# Sheet2.net
KiCad netlist of a schematic drawn in Altium Designer
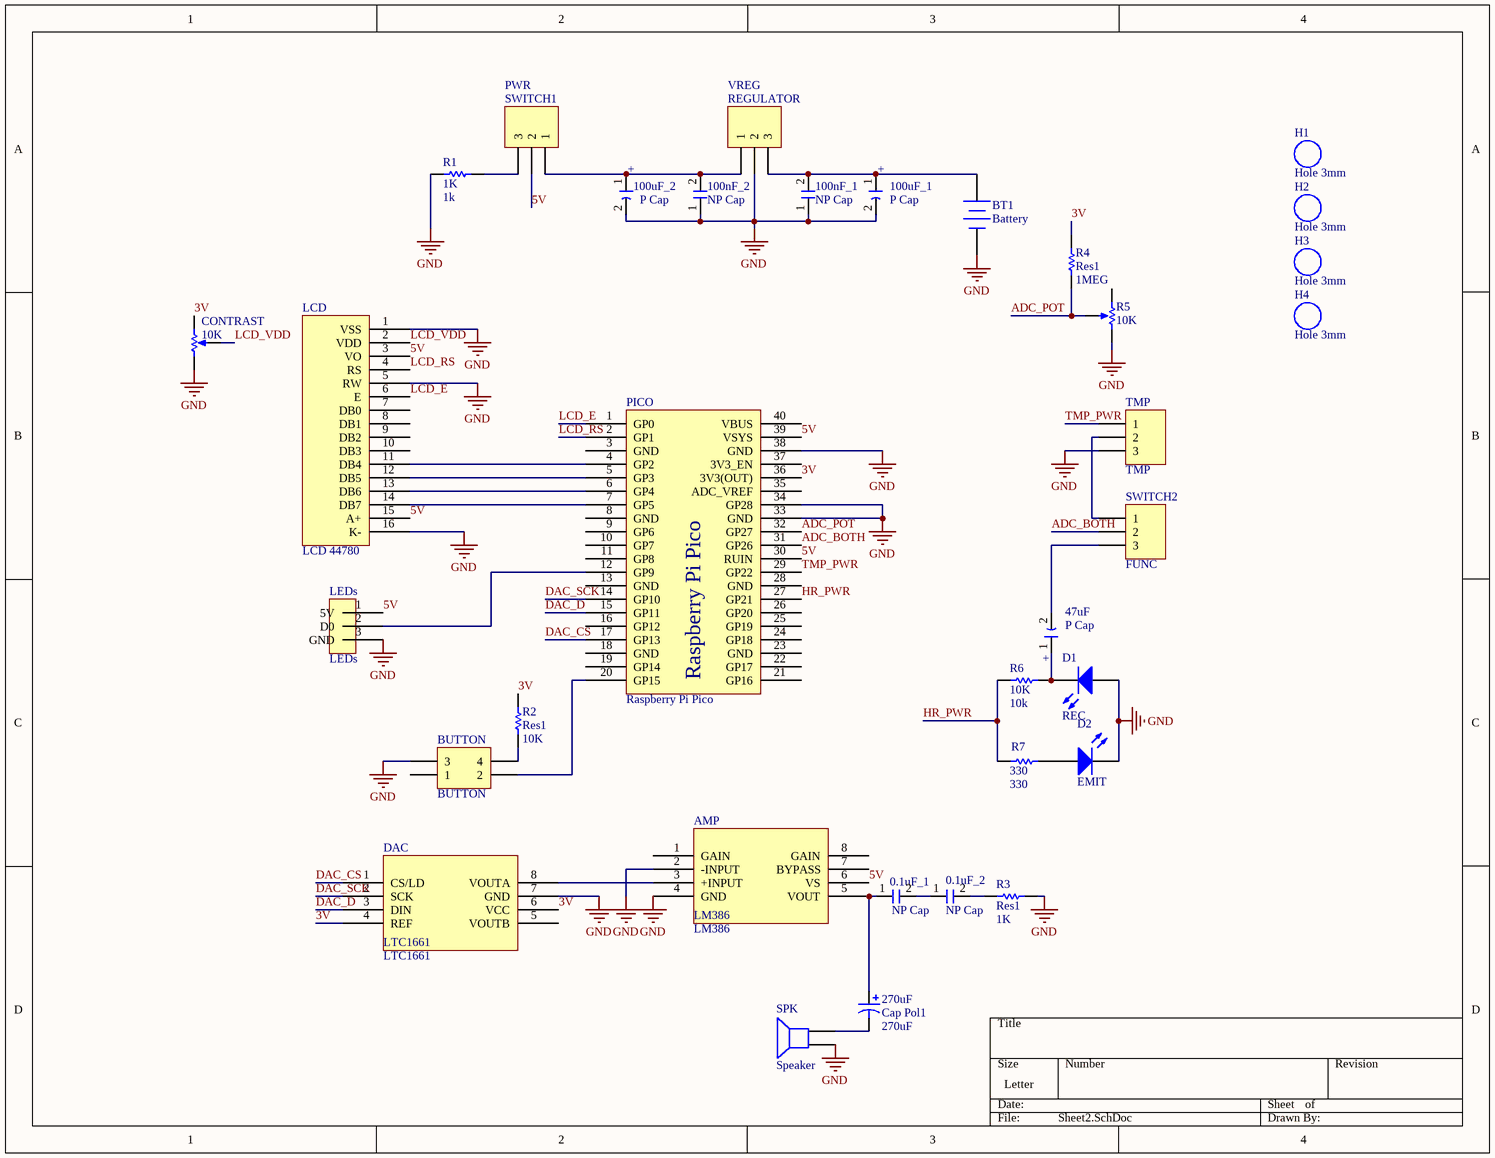
[diagram p0: Sheet2.SchDoc]

(export (version "E")
  (design (tool "Eeschema 10.0.6"))
  (components
    (comp (ref "0.1uF_1")
      (value "NP Cap")
      (footprint "NP Cap - Small")
      (libsource (lib "Custom_Schematics") (part "NP Cap"))
    )
    (comp (ref "0.1uF_2")
      (value "NP Cap")
      (footprint "NP Cap - Small")
      (libsource (lib "Custom_Schematics") (part "NP Cap"))
    )
    (comp (ref "47uF")
      (value "P Cap")
      (footprint "P Cap - Small")
      (libsource (lib "Custom_Schematics") (part "P Cap"))
    )
    (comp (ref "100nF_1")
      (value "NP Cap")
      (footprint "NP Cap - Small")
      (libsource (lib "Custom_Schematics") (part "NP Cap"))
    )
    (comp (ref "100nF_2")
      (value "NP Cap")
      (footprint "NP Cap - Small")
      (libsource (lib "Custom_Schematics") (part "NP Cap"))
    )
    (comp (ref "100uF_1")
      (value "P Cap")
      (footprint "P Cap - Small")
      (libsource (lib "Custom_Schematics") (part "P Cap"))
    )
    (comp (ref "100uF_2")
      (value "P Cap")
      (footprint "P Cap - Small")
      (libsource (lib "Custom_Schematics") (part "P Cap"))
    )
    (comp (ref "270uF")
      (value "Cap Pol1")
      (footprint "RB7.6-15")
      (description "Polarized Capacitor (Radial)")
      (fields (field (name "ALTIUM_VALUE") "270uF") (field (name "PUBLISHER") "Altium Limited"))
      (libsource (lib "Miscellaneous Devices") (part "Cap Pol1"))
    )
    (comp (ref "AMP") (value "LM386") (footprint "8DIP") (libsource (lib "Custom_Schematics") (part "LM386")))
    (comp (ref "BT1")
      (value "Battery")
      (footprint "BAT-2")
      (description "Multicell Battery")
      (fields (field (name "PUBLISHER") "Altium Limited"))
      (libsource (lib "Miscellaneous Devices") (part "Battery"))
    )
    (comp (ref "BUTTON")
      (value "BUTTON")
      (footprint "HDR2X2")
      (description "Header, 2-Pin, Dual row")
      (fields (field (name "PUBLISHER") "Altium Limited"))
      (libsource (lib "Miscellaneous Connectors") (part "Header 2X2"))
    )
    (comp (ref "CONTRAST")
      (value "10K")
      (footprint "POT OFFSET 200")
      (description "Potentiometer")
      (fields (field (name "Comment") "RPot_3") (field (name "PUBLISHER") "Altium Limited"))
      (libsource (lib "ECE Lib 22") (part "RPot"))
    )
    (comp (ref "D1")
      (value "REC")
      (footprint "LED-1")
      (description "Typical RED GaAs LED")
      (fields (field (name "PUBLISHER") "Altium Limited"))
      (libsource (lib "Miscellaneous Devices") (part "LED1"))
    )
    (comp (ref "D2")
      (value "EMIT")
      (footprint "LED-1")
      (description "Typical RED GaAs LED")
      (fields (field (name "PUBLISHER") "Altium Limited"))
      (libsource (lib "Miscellaneous Devices") (part "LED1"))
    )
    (comp (ref "DAC")
      (value "LTC1661")
      (footprint "8DIP")
      (libsource (lib "Custom_Schematics") (part "LTC1661"))
    )
    (comp (ref "H1")
      (value "Hole 3mm")
      (footprint "Hole 3mm")
      (libsource (lib "ECE Lib 22") (part "Hole 3mm"))
    )
    (comp (ref "H2")
      (value "Hole 3mm")
      (footprint "Hole 3mm")
      (libsource (lib "ECE Lib 22") (part "Hole 3mm"))
    )
    (comp (ref "H3")
      (value "Hole 3mm")
      (footprint "Hole 3mm")
      (libsource (lib "ECE Lib 22") (part "Hole 3mm"))
    )
    (comp (ref "H4")
      (value "Hole 3mm")
      (footprint "Hole 3mm")
      (libsource (lib "ECE Lib 22") (part "Hole 3mm"))
    )
    (comp (ref "LCD")
      (value "LCD 44780")
      (footprint "OLED 16x2")
      (libsource (lib "ECE Lib 22") (part "LCD 44780"))
    )
    (comp (ref "LEDs")
      (value "LEDs")
      (footprint "RGB LED Port")
      (libsource (lib "Custom_Schematics") (part "RGB LED Header"))
    )
    (comp (ref "PICO")
      (value "Raspberry Pi Pico")
      (footprint "Raspberry Pi Pico")
      (libsource (lib "ECE Lib 22") (part "Raspberry Pi Pico"))
    )
    (comp (ref "R1")
      (value "1K")
      (footprint "AXIAL-0.3")
      (description "Resistor")
      (fields (field (name "ALTIUM_VALUE") "1k") (field (name "PUBLISHER") "Altium Limited"))
      (libsource (lib "Miscellaneous Devices") (part "Res1"))
    )
    (comp (ref "R2")
      (value "Res1")
      (footprint "AXIAL-0.3")
      (description "Resistor")
      (fields (field (name "ALTIUM_VALUE") "10K") (field (name "PUBLISHER") "Altium Limited"))
      (libsource (lib "Miscellaneous Devices") (part "Res1"))
    )
    (comp (ref "R3")
      (value "Res1")
      (footprint "AXIAL-0.3")
      (description "Resistor")
      (fields (field (name "ALTIUM_VALUE") "1K") (field (name "PUBLISHER") "Altium Limited"))
      (libsource (lib "Miscellaneous Devices") (part "Res1"))
    )
    (comp (ref "R4")
      (value "Res1")
      (footprint "AXIAL-0.3")
      (description "Resistor")
      (fields (field (name "ALTIUM_VALUE") "1MEG") (field (name "PUBLISHER") "Altium Limited"))
      (libsource (lib "Miscellaneous Devices") (part "Res1"))
    )
    (comp (ref "R5")
      (value "10K")
      (footprint "POT OFFSET 200")
      (description "Potentiometer")
      (fields (field (name "Comment") "RPot_3") (field (name "PUBLISHER") "Altium Limited"))
      (libsource (lib "ECE Lib 22") (part "RPot"))
    )
    (comp (ref "R6")
      (value "10K")
      (footprint "AXIAL-0.3")
      (description "Resistor")
      (fields (field (name "ALTIUM_VALUE") "10k") (field (name "PUBLISHER") "Altium Limited"))
      (libsource (lib "Miscellaneous Devices") (part "Res1"))
    )
    (comp (ref "R7")
      (value "330")
      (footprint "AXIAL-0.3")
      (description "Resistor")
      (fields (field (name "ALTIUM_VALUE") "330") (field (name "PUBLISHER") "Altium Limited"))
      (libsource (lib "Miscellaneous Devices") (part "Res1"))
    )
    (comp (ref "REGULATOR")
      (value "VREG")
      (footprint "HDR1X3")
      (description "Header, 3-Pin")
      (fields (field (name "PUBLISHER") "Altium Limited"))
      (libsource (lib "Miscellaneous Connectors") (part "Header 3"))
    )
    (comp (ref "SPK")
      (value "Speaker")
      (footprint "PIN2")
      (description "Loudspeaker")
      (fields (field (name "PUBLISHER") "Altium Limited"))
      (libsource (lib "Miscellaneous Devices") (part "Speaker"))
    )
    (comp (ref "SWITCH1")
      (value "PWR")
      (footprint "HDR1X3")
      (description "Header, 3-Pin")
      (fields (field (name "PUBLISHER") "Altium Limited"))
      (libsource (lib "") (part "Header 3_1"))
    )
    (comp (ref "SWITCH2")
      (value "FUNC")
      (footprint "HDR1X3")
      (description "Header, 3-Pin")
      (fields (field (name "PUBLISHER") "Altium Limited"))
      (libsource (lib "") (part "Header 3_1"))
    )
    (comp (ref "TMP")
      (value "TMP")
      (footprint "HDR1X3")
      (description "Header, 3-Pin")
      (fields (field (name "PUBLISHER") "Altium Limited"))
      (libsource (lib "") (part "Header 3_1"))
    )
  )
  (nets
    (net (code "1") (name "/3V") (class "Default")
      (node (ref "CONTRAST") (pin "3") (pinfunction "BOT_3") (pintype "passive"))
      (node (ref "DAC") (pin "4") (pinfunction "REF_4") (pintype "passive"))
      (node (ref "DAC") (pin "6") (pinfunction "VCC_6") (pintype "passive"))
      (node (ref "PICO") (pin "36") (pinfunction "3V3(OUT)_36") (pintype "passive"))
      (node (ref "R2") (pin "2") (pinfunction "2_2") (pintype "passive"))
      (node (ref "R4") (pin "1") (pinfunction "1_1") (pintype "passive"))
    )
    (net (code "2") (name "/5V") (class "Default")
      (node (ref "AMP") (pin "6") (pinfunction "VS_6") (pintype "passive"))
      (node (ref "LCD") (pin "15") (pinfunction "A+_15") (pintype "passive"))
      (node (ref "LCD") (pin "3") (pinfunction "VO_3") (pintype "passive"))
      (node (ref "LEDs") (pin "1") (pinfunction "5V_1") (pintype "passive"))
      (node (ref "PICO") (pin "30") (pinfunction "RUIN_30") (pintype "passive"))
      (node (ref "PICO") (pin "39") (pinfunction "VSYS_39") (pintype "passive"))
      (node (ref "SWITCH1") (pin "2") (pinfunction "2_2") (pintype "passive"))
    )
    (net (code "3") (name "/ADC_BOTH") (class "Default")
      (node (ref "PICO") (pin "31") (pinfunction "GP26_31") (pintype "passive"))
      (node (ref "SWITCH2") (pin "2") (pinfunction "2_2") (pintype "passive"))
    )
    (net (code "4") (name "/ADC_POT") (class "Default")
      (node (ref "PICO") (pin "32") (pinfunction "GP27_32") (pintype "passive"))
      (node (ref "R4") (pin "2") (pinfunction "2_2") (pintype "passive"))
      (node (ref "R5") (pin "2") (pinfunction "TAP_2") (pintype "passive"))
    )
    (net (code "5") (name "/DAC_CS") (class "Default")
      (node (ref "DAC") (pin "1") (pinfunction "CS/LD_1") (pintype "passive"))
      (node (ref "PICO") (pin "17") (pinfunction "GP13_17") (pintype "passive"))
    )
    (net (code "6") (name "/DAC_D") (class "Default")
      (node (ref "DAC") (pin "3") (pinfunction "DIN_3") (pintype "passive"))
      (node (ref "PICO") (pin "15") (pinfunction "GP11_15") (pintype "passive"))
    )
    (net (code "7") (name "/DAC_SCK") (class "Default")
      (node (ref "DAC") (pin "2") (pinfunction "SCK_2") (pintype "passive"))
      (node (ref "PICO") (pin "14") (pinfunction "GP10_14") (pintype "passive"))
    )
    (net (code "8") (name "/HR_PWR") (class "Default")
      (node (ref "PICO") (pin "27") (pinfunction "GP21_27") (pintype "passive"))
      (node (ref "R6") (pin "2") (pinfunction "2_2") (pintype "passive"))
      (node (ref "R7") (pin "2") (pinfunction "2_2") (pintype "passive"))
    )
    (net (code "9") (name "/LCD_E") (class "Default")
      (node (ref "LCD") (pin "6") (pinfunction "E_6") (pintype "passive"))
      (node (ref "PICO") (pin "1") (pinfunction "GP0_1") (pintype "passive"))
    )
    (net (code "10") (name "/LCD_RS") (class "Default")
      (node (ref "LCD") (pin "4") (pinfunction "RS_4") (pintype "passive"))
      (node (ref "PICO") (pin "2") (pinfunction "GP1_2") (pintype "passive"))
    )
    (net (code "11") (name "/LCD_VDD") (class "Default")
      (node (ref "CONTRAST") (pin "2") (pinfunction "TAP_2") (pintype "passive"))
      (node (ref "LCD") (pin "2") (pinfunction "VDD_2") (pintype "passive"))
    )
    (net (code "12") (name "/TMP_PWR") (class "Default")
      (node (ref "PICO") (pin "29") (pinfunction "GP22_29") (pintype "passive"))
      (node (ref "TMP") (pin "1") (pinfunction "1_1") (pintype "passive"))
    )
    (net (code "13") (name "GND") (class "Default")
      (node (ref "100nF_1") (pin "1") (pinfunction "1_1") (pintype "passive"))
      (node (ref "100nF_2") (pin "1") (pinfunction "1_1") (pintype "passive"))
      (node (ref "100uF_1") (pin "2") (pinfunction "2_2") (pintype "passive"))
      (node (ref "100uF_2") (pin "2") (pinfunction "2_2") (pintype "passive"))
      (node (ref "AMP") (pin "2") (pinfunction "-INPUT_2") (pintype "passive"))
      (node (ref "AMP") (pin "4") (pinfunction "GND_4") (pintype "passive"))
      (node (ref "BT1") (pin "2") (pinfunction "-_2") (pintype "passive"))
      (node (ref "BUTTON") (pin "3") (pinfunction "3_3") (pintype "passive"))
      (node (ref "CONTRAST") (pin "1") (pinfunction "TOP_1") (pintype "passive"))
      (node (ref "D1") (pin "1") (pinfunction "A_1") (pintype "passive"))
      (node (ref "D2") (pin "2") (pinfunction "K_2") (pintype "passive"))
      (node (ref "DAC") (pin "7") (pinfunction "GND_7") (pintype "passive"))
      (node (ref "LCD") (pin "1") (pinfunction "VSS_1") (pintype "passive"))
      (node (ref "LCD") (pin "16") (pinfunction "K-_16") (pintype "passive"))
      (node (ref "LCD") (pin "5") (pinfunction "RW_5") (pintype "passive"))
      (node (ref "LEDs") (pin "3") (pinfunction "GND_3") (pintype "passive"))
      (node (ref "PICO") (pin "33") (pinfunction "GND_33") (pintype "passive"))
      (node (ref "PICO") (pin "34") (pinfunction "GP28_34") (pintype "passive"))
      (node (ref "PICO") (pin "38") (pinfunction "GND_38") (pintype "passive"))
      (node (ref "R1") (pin "1") (pinfunction "1_1") (pintype "passive"))
      (node (ref "R3") (pin "1") (pinfunction "1_1") (pintype "passive"))
      (node (ref "R5") (pin "3") (pinfunction "BOT_3") (pintype "passive"))
      (node (ref "REGULATOR") (pin "2") (pinfunction "2_2") (pintype "passive"))
      (node (ref "SPK") (pin "2") (pinfunction "2_2") (pintype "passive"))
      (node (ref "TMP") (pin "3") (pinfunction "3_3") (pintype "passive"))
    )
    (net (code "14") (name "Net-(0.1uF_1-Pad2)") (class "Default")
      (node (ref "0.1uF_1") (pin "2") (pinfunction "2_2") (pintype "passive"))
      (node (ref "0.1uF_2") (pin "1") (pinfunction "1_1") (pintype "passive"))
    )
    (net (code "15") (name "Net-(0.1uF_2-Pad2)") (class "Default")
      (node (ref "0.1uF_2") (pin "2") (pinfunction "2_2") (pintype "passive"))
      (node (ref "R3") (pin "2") (pinfunction "2_2") (pintype "passive"))
    )
    (net (code "16") (name "Net-(47uF-Pad2)") (class "Default")
      (node (ref "47uF") (pin "2") (pinfunction "2_2") (pintype "passive"))
      (node (ref "SWITCH2") (pin "3") (pinfunction "3_3") (pintype "passive"))
    )
    (net (code "17") (name "Net-(100nF_2-Pad2)") (class "Default")
      (node (ref "100nF_2") (pin "2") (pinfunction "2_2") (pintype "passive"))
      (node (ref "100uF_2") (pin "1") (pinfunction "1_1") (pintype "passive"))
      (node (ref "REGULATOR") (pin "1") (pinfunction "1_1") (pintype "passive"))
      (node (ref "SWITCH1") (pin "1") (pinfunction "1_1") (pintype "passive"))
    )
    (net (code "18") (name "Net-(270uF-Pad2)") (class "Default")
      (node (ref "270uF") (pin "2") (pinfunction "2_2") (pintype "passive"))
      (node (ref "SPK") (pin "1") (pinfunction "1_1") (pintype "passive"))
    )
    (net (code "19") (name "Net-(AMP-+INPUT)") (class "Default")
      (node (ref "AMP") (pin "3") (pinfunction "+INPUT_3") (pintype "passive"))
      (node (ref "DAC") (pin "8") (pinfunction "VOUTA_8") (pintype "passive"))
    )
    (net (code "20") (name "Net-(AMP-VOUT)") (class "Default")
      (node (ref "0.1uF_1") (pin "1") (pinfunction "1_1") (pintype "passive"))
      (node (ref "270uF") (pin "1") (pinfunction "1_1") (pintype "passive"))
      (node (ref "AMP") (pin "5") (pinfunction "VOUT_5") (pintype "passive"))
    )
    (net (code "21") (name "Net-(BT1-+)") (class "Default")
      (node (ref "100nF_1") (pin "2") (pinfunction "2_2") (pintype "passive"))
      (node (ref "100uF_1") (pin "1") (pinfunction "1_1") (pintype "passive"))
      (node (ref "BT1") (pin "1") (pinfunction "+_1") (pintype "passive"))
      (node (ref "REGULATOR") (pin "3") (pinfunction "3_3") (pintype "passive"))
    )
    (net (code "22") (name "Net-(BUTTON-Pad4)") (class "Default")
      (node (ref "BUTTON") (pin "4") (pinfunction "4_4") (pintype "passive"))
      (node (ref "R2") (pin "1") (pinfunction "1_1") (pintype "passive"))
    )
    (net (code "23") (name "Net-(D1-K)") (class "Default")
      (node (ref "47uF") (pin "1") (pinfunction "1_1") (pintype "passive"))
      (node (ref "D1") (pin "2") (pinfunction "K_2") (pintype "passive"))
      (node (ref "R6") (pin "1") (pinfunction "1_1") (pintype "passive"))
    )
    (net (code "24") (name "Net-(D2-A)") (class "Default")
      (node (ref "D2") (pin "1") (pinfunction "A_1") (pintype "passive"))
      (node (ref "R7") (pin "1") (pinfunction "1_1") (pintype "passive"))
    )
    (net (code "25") (name "Net-(LCD-DB4)") (class "Default")
      (node (ref "LCD") (pin "11") (pinfunction "DB4_11") (pintype "passive"))
      (node (ref "PICO") (pin "4") (pinfunction "GP2_4") (pintype "passive"))
    )
    (net (code "26") (name "Net-(LCD-DB5)") (class "Default")
      (node (ref "LCD") (pin "12") (pinfunction "DB5_12") (pintype "passive"))
      (node (ref "PICO") (pin "5") (pinfunction "GP3_5") (pintype "passive"))
    )
    (net (code "27") (name "Net-(LCD-DB6)") (class "Default")
      (node (ref "LCD") (pin "13") (pinfunction "DB6_13") (pintype "passive"))
      (node (ref "PICO") (pin "6") (pinfunction "GP4_6") (pintype "passive"))
    )
    (net (code "28") (name "Net-(LCD-DB7)") (class "Default")
      (node (ref "LCD") (pin "14") (pinfunction "DB7_14") (pintype "passive"))
      (node (ref "PICO") (pin "7") (pinfunction "GP5_7") (pintype "passive"))
    )
    (net (code "29") (name "Net-(LEDs-D0)") (class "Default")
      (node (ref "LEDs") (pin "2") (pinfunction "D0_2") (pintype "passive"))
      (node (ref "PICO") (pin "12") (pinfunction "GP9_12") (pintype "passive"))
    )
    (net (code "30") (name "Net-(PICO-GP15)") (class "Default")
      (node (ref "BUTTON") (pin "2") (pinfunction "2_2") (pintype "passive"))
      (node (ref "PICO") (pin "20") (pinfunction "GP15_20") (pintype "passive"))
    )
    (net (code "31") (name "Net-(R1-Pad2)") (class "Default")
      (node (ref "R1") (pin "2") (pinfunction "2_2") (pintype "passive"))
      (node (ref "SWITCH1") (pin "3") (pinfunction "3_3") (pintype "passive"))
    )
    (net (code "32") (name "Net-(SWITCH2-Pad1)") (class "Default")
      (node (ref "SWITCH2") (pin "1") (pinfunction "1_1") (pintype "passive"))
      (node (ref "TMP") (pin "2") (pinfunction "2_2") (pintype "passive"))
    )
    (net (code "33") (name "unconnected-(AMP-BYPASS-Pad7)") (class "Default")
      (node (ref "AMP") (pin "7") (pinfunction "BYPASS_7") (pintype "passive"))
    )
    (net (code "34") (name "unconnected-(AMP-GAIN-Pad1)") (class "Default")
      (node (ref "AMP") (pin "1") (pinfunction "GAIN_1") (pintype "passive"))
    )
    (net (code "35") (name "unconnected-(AMP-GAIN-Pad8)") (class "Default")
      (node (ref "AMP") (pin "8") (pinfunction "GAIN_8") (pintype "passive"))
    )
    (net (code "36") (name "unconnected-(BUTTON-Pad1)") (class "Default")
      (node (ref "BUTTON") (pin "1") (pinfunction "1_1") (pintype "passive"))
    )
    (net (code "37") (name "unconnected-(DAC-VOUTB-Pad5)") (class "Default")
      (node (ref "DAC") (pin "5") (pinfunction "VOUTB_5") (pintype "passive"))
    )
    (net (code "38") (name "unconnected-(LCD-DB0-Pad7)") (class "Default")
      (node (ref "LCD") (pin "7") (pinfunction "DB0_7") (pintype "passive"))
    )
    (net (code "39") (name "unconnected-(LCD-DB1-Pad8)") (class "Default")
      (node (ref "LCD") (pin "8") (pinfunction "DB1_8") (pintype "passive"))
    )
    (net (code "40") (name "unconnected-(LCD-DB2-Pad9)") (class "Default")
      (node (ref "LCD") (pin "9") (pinfunction "DB2_9") (pintype "passive"))
    )
    (net (code "41") (name "unconnected-(LCD-DB3-Pad10)") (class "Default")
      (node (ref "LCD") (pin "10") (pinfunction "DB3_10") (pintype "passive"))
    )
    (net (code "42") (name "unconnected-(PICO-3V3_EN-Pad37)") (class "Default")
      (node (ref "PICO") (pin "37") (pinfunction "3V3_EN_37") (pintype "passive"))
    )
    (net (code "43") (name "unconnected-(PICO-ADC_VREF-Pad35)") (class "Default")
      (node (ref "PICO") (pin "35") (pinfunction "ADC_VREF_35") (pintype "passive"))
    )
    (net (code "44") (name "unconnected-(PICO-GND-Pad3)") (class "Default")
      (node (ref "PICO") (pin "3") (pinfunction "GND_3") (pintype "passive"))
    )
    (net (code "45") (name "unconnected-(PICO-GND-Pad8)") (class "Default")
      (node (ref "PICO") (pin "8") (pinfunction "GND_8") (pintype "passive"))
    )
    (net (code "46") (name "unconnected-(PICO-GND-Pad13)") (class "Default")
      (node (ref "PICO") (pin "13") (pinfunction "GND_13") (pintype "passive"))
    )
    (net (code "47") (name "unconnected-(PICO-GND-Pad18)") (class "Default")
      (node (ref "PICO") (pin "18") (pinfunction "GND_18") (pintype "passive"))
    )
    (net (code "48") (name "unconnected-(PICO-GND-Pad23)") (class "Default")
      (node (ref "PICO") (pin "23") (pinfunction "GND_23") (pintype "passive"))
    )
    (net (code "49") (name "unconnected-(PICO-GND-Pad28)") (class "Default")
      (node (ref "PICO") (pin "28") (pinfunction "GND_28") (pintype "passive"))
    )
    (net (code "50") (name "unconnected-(PICO-GP6-Pad9)") (class "Default")
      (node (ref "PICO") (pin "9") (pinfunction "GP6_9") (pintype "passive"))
    )
    (net (code "51") (name "unconnected-(PICO-GP7-Pad10)") (class "Default")
      (node (ref "PICO") (pin "10") (pinfunction "GP7_10") (pintype "passive"))
    )
    (net (code "52") (name "unconnected-(PICO-GP8-Pad11)") (class "Default")
      (node (ref "PICO") (pin "11") (pinfunction "GP8_11") (pintype "passive"))
    )
    (net (code "53") (name "unconnected-(PICO-GP12-Pad16)") (class "Default")
      (node (ref "PICO") (pin "16") (pinfunction "GP12_16") (pintype "passive"))
    )
    (net (code "54") (name "unconnected-(PICO-GP14-Pad19)") (class "Default")
      (node (ref "PICO") (pin "19") (pinfunction "GP14_19") (pintype "passive"))
    )
    (net (code "55") (name "unconnected-(PICO-GP16-Pad21)") (class "Default")
      (node (ref "PICO") (pin "21") (pinfunction "GP16_21") (pintype "passive"))
    )
    (net (code "56") (name "unconnected-(PICO-GP17-Pad22)") (class "Default")
      (node (ref "PICO") (pin "22") (pinfunction "GP17_22") (pintype "passive"))
    )
    (net (code "57") (name "unconnected-(PICO-GP18-Pad24)") (class "Default")
      (node (ref "PICO") (pin "24") (pinfunction "GP18_24") (pintype "passive"))
    )
    (net (code "58") (name "unconnected-(PICO-GP19-Pad25)") (class "Default")
      (node (ref "PICO") (pin "25") (pinfunction "GP19_25") (pintype "passive"))
    )
    (net (code "59") (name "unconnected-(PICO-GP20-Pad26)") (class "Default")
      (node (ref "PICO") (pin "26") (pinfunction "GP20_26") (pintype "passive"))
    )
    (net (code "60") (name "unconnected-(PICO-VBUS-Pad40)") (class "Default")
      (node (ref "PICO") (pin "40") (pinfunction "VBUS_40") (pintype "passive"))
    )
    (net (code "61") (name "unconnected-(R5-TOP-Pad1)") (class "Default")
      (node (ref "R5") (pin "1") (pinfunction "TOP_1") (pintype "passive"))
    )
  )
)
